# ESP_Ambient_sensors.net
KiCad netlist of a schematic drawn in EAGLE
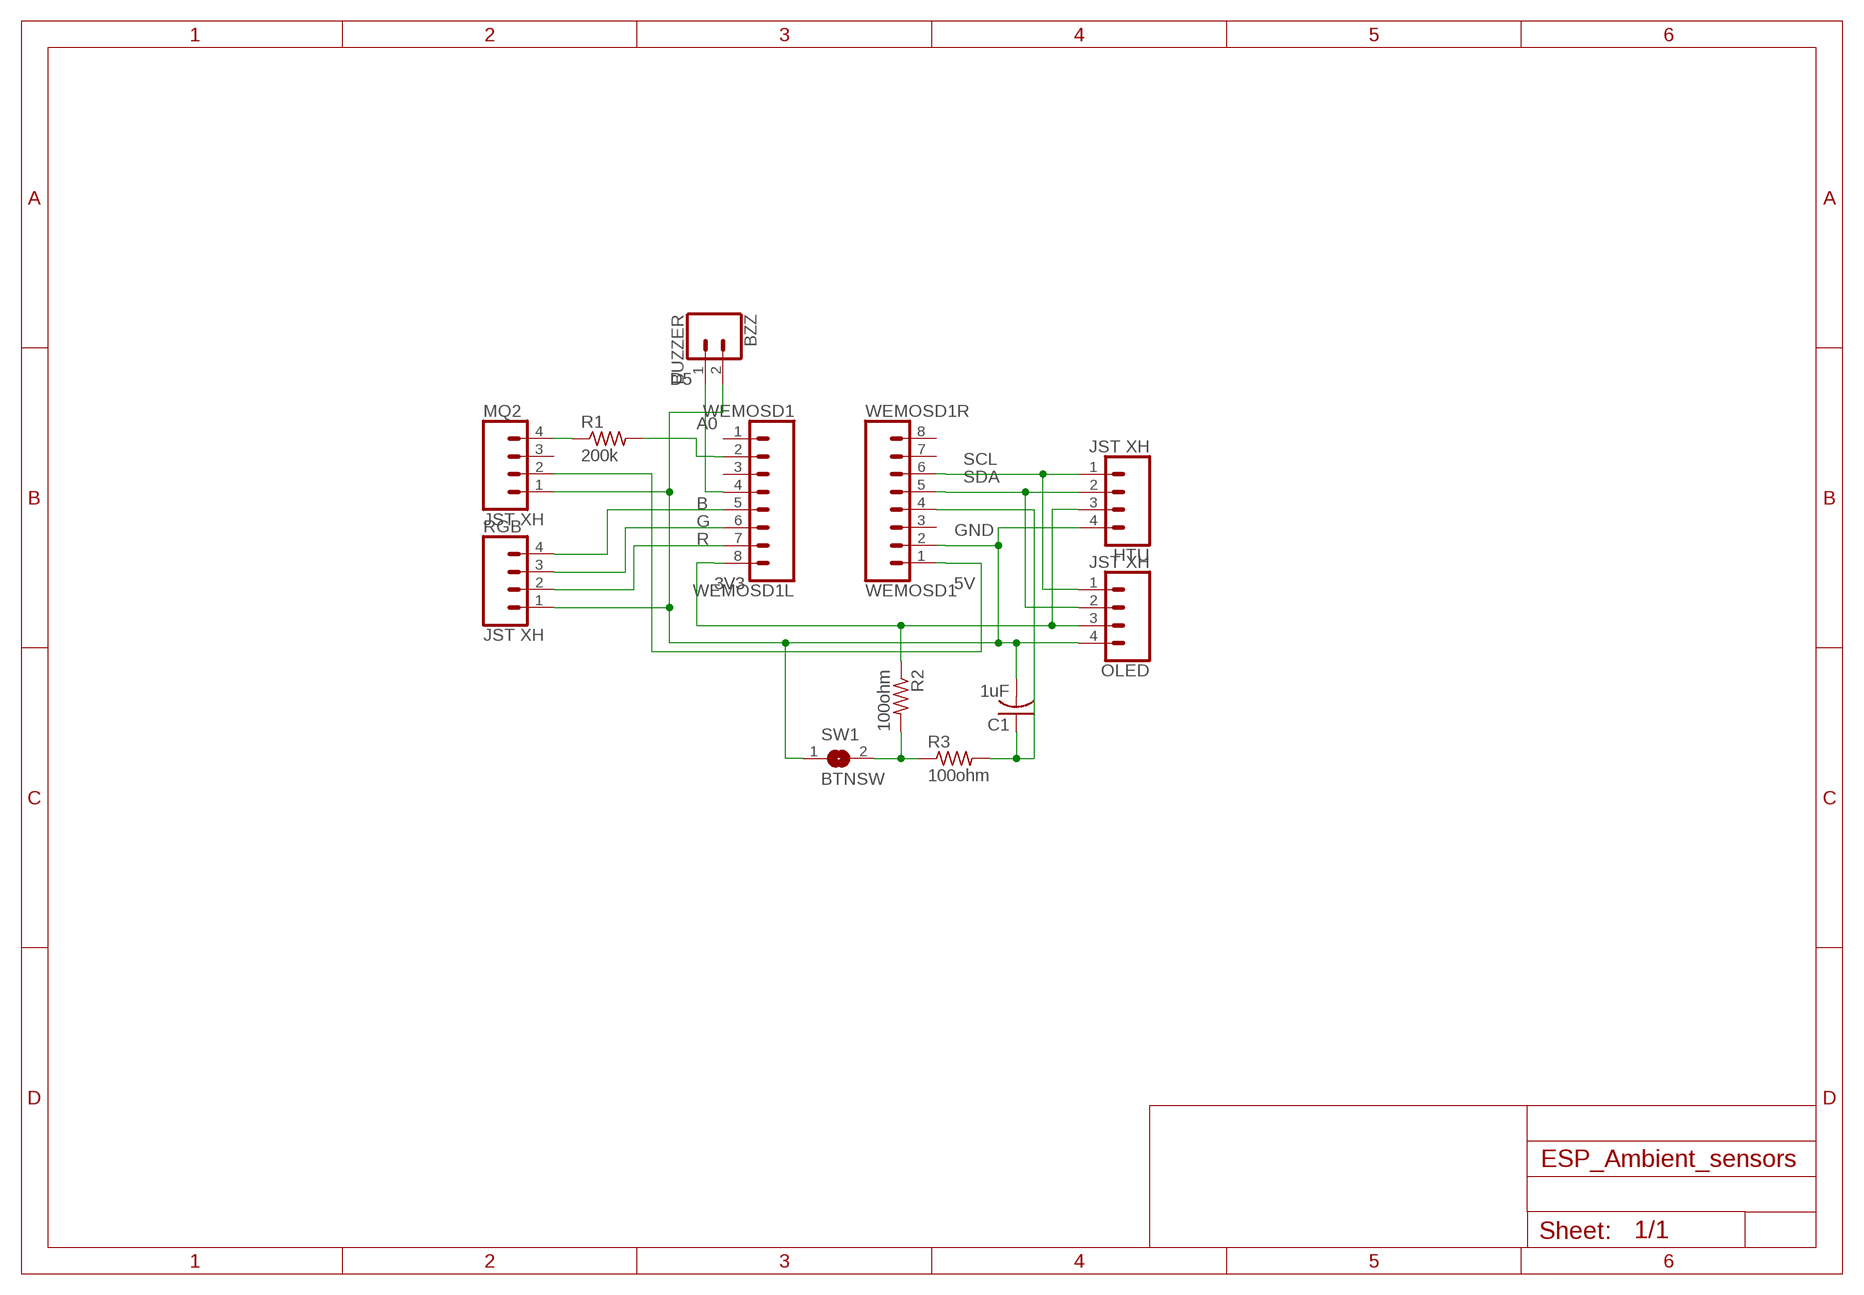
[diagram p0: schematic, sheet 1]

(export (version "E")
  (design (tool "Eeschema 10.0.6"))
  (components
    (comp (ref "BZZ")
      (value "BUZZER")
      (footprint "eagle-import:1X02")
      (libsource (lib "eagle-import") (part "CONN_02"))
    )
    (comp (ref "C1")
      (value "1uF")
      (footprint "eagle-import:C0805")
      (libsource (lib "eagle-import") (part "C-USC0805"))
    )
    (comp (ref "HTU")
      (value "JST XH")
      (footprint "eagle-import:1X04")
      (libsource (lib "eagle-import") (part "CONN_04"))
    )
    (comp (ref "MQ2")
      (value "JST XH")
      (footprint "eagle-import:1X04")
      (libsource (lib "eagle-import") (part "CONN_04"))
    )
    (comp (ref "OLED")
      (value "JST XH")
      (footprint "eagle-import:1X04")
      (libsource (lib "eagle-import") (part "CONN_04"))
    )
    (comp (ref "R1")
      (value "200k")
      (footprint "eagle-import:R0805")
      (libsource (lib "eagle-import") (part "R-US_R0805"))
    )
    (comp (ref "R2")
      (value "100ohm")
      (footprint "eagle-import:R0805")
      (libsource (lib "eagle-import") (part "R-US_R0805"))
    )
    (comp (ref "R3")
      (value "100ohm")
      (footprint "eagle-import:R0805")
      (libsource (lib "eagle-import") (part "R-US_R0805"))
    )
    (comp (ref "RGB")
      (value "JST XH")
      (footprint "eagle-import:1X04")
      (libsource (lib "eagle-import") (part "CONN_04"))
    )
    (comp (ref "SW1")
      (value "BTNSW")
      (footprint "eagle-import:SJW")
      (libsource (lib "eagle-import") (part "SJW"))
    )
    (comp (ref "WEMOSD1L")
      (value "WEMOSD1")
      (footprint "eagle-import:1X08")
      (libsource (lib "eagle-import") (part "CONN_08{dblquote}"))
    )
    (comp (ref "WEMOSD1R")
      (value "WEMOSD1")
      (footprint "eagle-import:1X08")
      (libsource (lib "eagle-import") (part "CONN_08{dblquote}"))
    )
  )
  (nets
    (net (code "1") (name "/3V3") (class "Default")
      (node (ref "HTU") (pin "3") (pinfunction "3_3") (pintype "passive"))
      (node (ref "OLED") (pin "3") (pinfunction "3_3") (pintype "passive"))
      (node (ref "R2") (pin "1") (pinfunction "1_1") (pintype "passive"))
      (node (ref "WEMOSD1L") (pin "8") (pinfunction "8_8") (pintype "passive"))
    )
    (net (code "2") (name "/5V") (class "Default")
      (node (ref "MQ2") (pin "2") (pinfunction "2_2") (pintype "passive"))
      (node (ref "WEMOSD1R") (pin "1") (pinfunction "1_1") (pintype "passive"))
    )
    (net (code "3") (name "/A0") (class "Default")
      (node (ref "R1") (pin "2") (pinfunction "2_2") (pintype "passive"))
      (node (ref "WEMOSD1L") (pin "2") (pinfunction "2_2") (pintype "passive"))
    )
    (net (code "4") (name "/B") (class "Default")
      (node (ref "RGB") (pin "4") (pinfunction "4_4") (pintype "passive"))
      (node (ref "WEMOSD1L") (pin "5") (pinfunction "5_5") (pintype "passive"))
    )
    (net (code "5") (name "/D5") (class "Default")
      (node (ref "BZZ") (pin "1") (pinfunction "1_1") (pintype "passive"))
      (node (ref "WEMOSD1L") (pin "4") (pinfunction "4_4") (pintype "passive"))
    )
    (net (code "6") (name "/G") (class "Default")
      (node (ref "RGB") (pin "3") (pinfunction "3_3") (pintype "passive"))
      (node (ref "WEMOSD1L") (pin "6") (pinfunction "6_6") (pintype "passive"))
    )
    (net (code "7") (name "/GND") (class "Default")
      (node (ref "BZZ") (pin "2") (pinfunction "2_2") (pintype "passive"))
      (node (ref "C1") (pin "2") (pinfunction "2_2") (pintype "passive"))
      (node (ref "HTU") (pin "4") (pinfunction "4_4") (pintype "passive"))
      (node (ref "MQ2") (pin "1") (pinfunction "1_1") (pintype "passive"))
      (node (ref "OLED") (pin "4") (pinfunction "4_4") (pintype "passive"))
      (node (ref "RGB") (pin "1") (pinfunction "1_1") (pintype "passive"))
      (node (ref "SW1") (pin "1") (pinfunction "1_1") (pintype "passive"))
      (node (ref "WEMOSD1R") (pin "2") (pinfunction "2_2") (pintype "passive"))
    )
    (net (code "8") (name "/R") (class "Default")
      (node (ref "RGB") (pin "2") (pinfunction "2_2") (pintype "passive"))
      (node (ref "WEMOSD1L") (pin "7") (pinfunction "7_7") (pintype "passive"))
    )
    (net (code "9") (name "/SCL") (class "Default")
      (node (ref "HTU") (pin "1") (pinfunction "1_1") (pintype "passive"))
      (node (ref "OLED") (pin "1") (pinfunction "1_1") (pintype "passive"))
      (node (ref "WEMOSD1R") (pin "6") (pinfunction "6_6") (pintype "passive"))
    )
    (net (code "10") (name "/SDA") (class "Default")
      (node (ref "HTU") (pin "2") (pinfunction "2_2") (pintype "passive"))
      (node (ref "OLED") (pin "2") (pinfunction "2_2") (pintype "passive"))
      (node (ref "WEMOSD1R") (pin "5") (pinfunction "5_5") (pintype "passive"))
    )
    (net (code "11") (name "Net-(C1-Pad1)") (class "Default")
      (node (ref "C1") (pin "1") (pinfunction "1_1") (pintype "passive"))
      (node (ref "R3") (pin "2") (pinfunction "2_2") (pintype "passive"))
      (node (ref "WEMOSD1R") (pin "4") (pinfunction "4_4") (pintype "passive"))
    )
    (net (code "12") (name "Net-(MQ2-Pad4)") (class "Default")
      (node (ref "MQ2") (pin "4") (pinfunction "4_4") (pintype "passive"))
      (node (ref "R1") (pin "1") (pinfunction "1_1") (pintype "passive"))
    )
    (net (code "13") (name "Net-(R2-Pad2)") (class "Default")
      (node (ref "R2") (pin "2") (pinfunction "2_2") (pintype "passive"))
      (node (ref "R3") (pin "1") (pinfunction "1_1") (pintype "passive"))
      (node (ref "SW1") (pin "2") (pinfunction "2_2") (pintype "passive"))
    )
    (net (code "14") (name "unconnected-(MQ2-Pad3)") (class "Default")
      (node (ref "MQ2") (pin "3") (pinfunction "3_3") (pintype "passive"))
    )
    (net (code "15") (name "unconnected-(WEMOSD1L-Pad1)") (class "Default")
      (node (ref "WEMOSD1L") (pin "1") (pinfunction "1_1") (pintype "passive"))
    )
    (net (code "16") (name "unconnected-(WEMOSD1L-Pad3)") (class "Default")
      (node (ref "WEMOSD1L") (pin "3") (pinfunction "3_3") (pintype "passive"))
    )
    (net (code "17") (name "unconnected-(WEMOSD1R-Pad3)") (class "Default")
      (node (ref "WEMOSD1R") (pin "3") (pinfunction "3_3") (pintype "passive"))
    )
    (net (code "18") (name "unconnected-(WEMOSD1R-Pad7)") (class "Default")
      (node (ref "WEMOSD1R") (pin "7") (pinfunction "7_7") (pintype "passive"))
    )
    (net (code "19") (name "unconnected-(WEMOSD1R-Pad8)") (class "Default")
      (node (ref "WEMOSD1R") (pin "8") (pinfunction "8_8") (pintype "passive"))
    )
  )
)
